# Power.net
KiCad netlist of a schematic drawn in Altium Designer
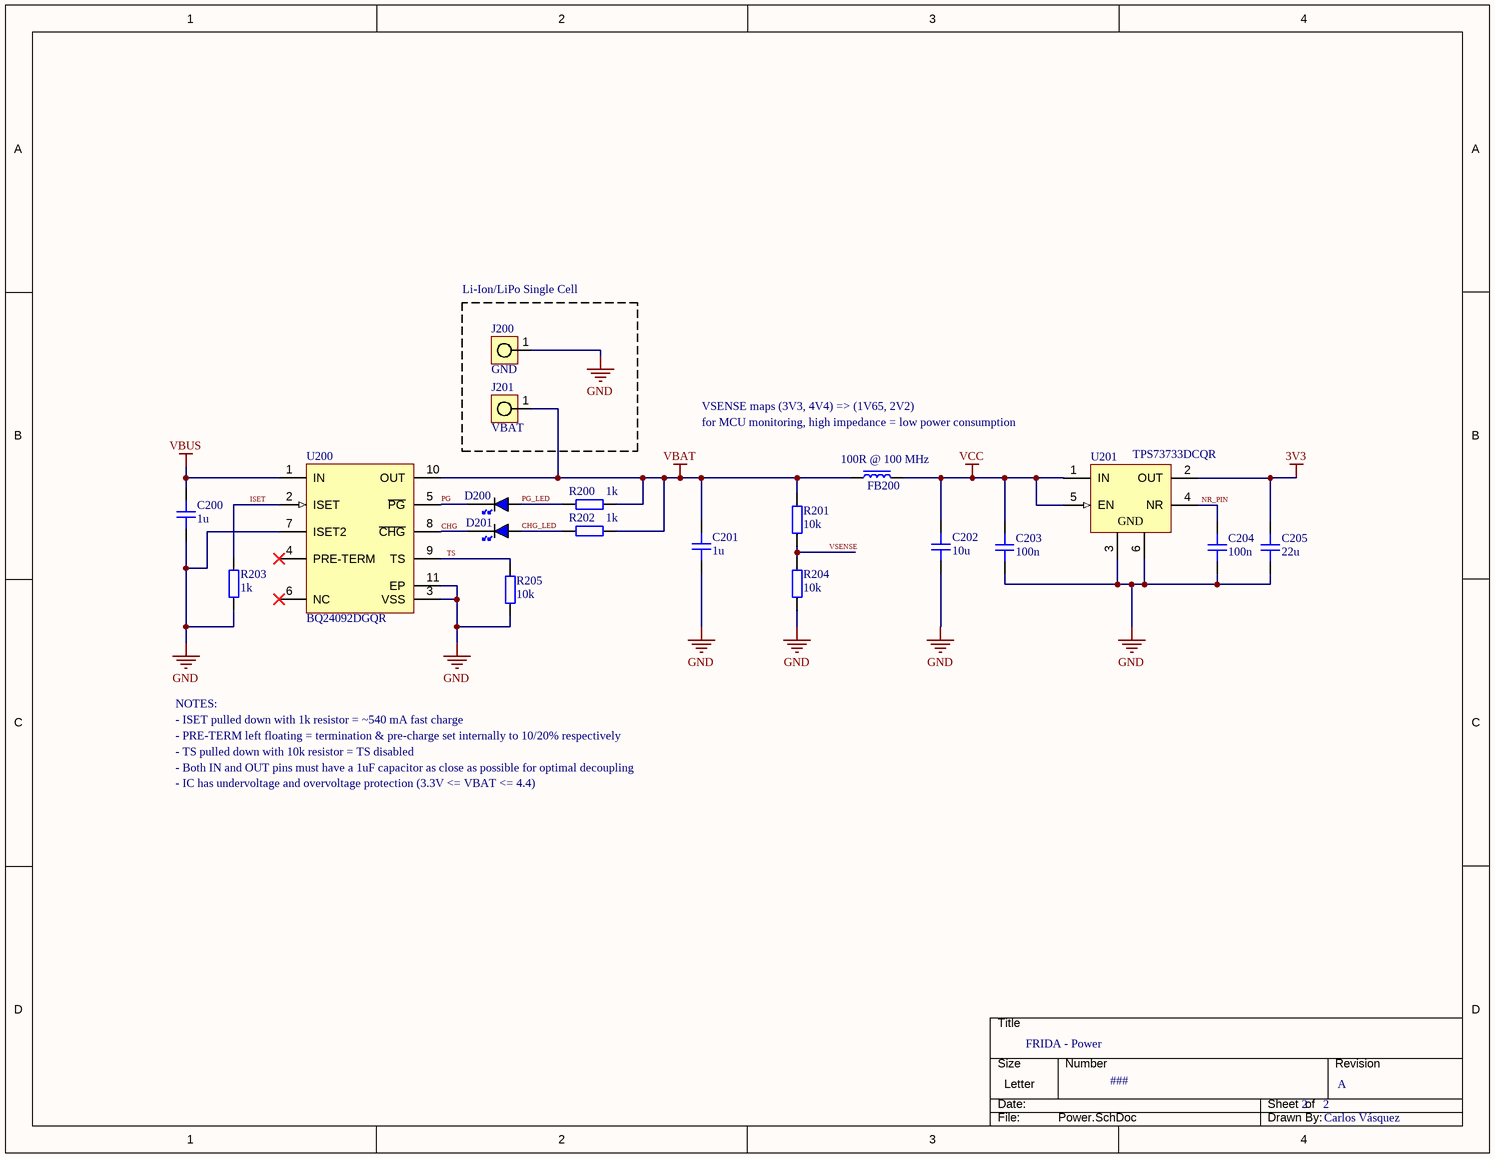
[diagram p0: Power.SchDoc]

(export (version "E")
  (design (tool "Eeschema 10.0.6"))
  (components
    (comp (ref "C200")
      (value "1u")
      (footprint "CAP_0402")
      (description "Capacitor SMD 0402")
      (libsource (lib "Schematic-Lib-PhilsLab") (part "CAP_0402"))
    )
    (comp (ref "C201")
      (value "1u")
      (footprint "CAP_0402")
      (description "Capacitor SMD 0402")
      (libsource (lib "Schematic-Lib-PhilsLab") (part "CAP_0402"))
    )
    (comp (ref "C202")
      (value "10u")
      (footprint "CAP_0805")
      (description "Capacitor SMD 0805")
      (libsource (lib "Schematic-Lib-PhilsLab") (part "CAP_0805"))
    )
    (comp (ref "C203")
      (value "100n")
      (footprint "CAP_0603")
      (description "Capacitor SMD 0603")
      (libsource (lib "Schematic-Lib-PhilsLab") (part "CAP_0603"))
    )
    (comp (ref "C204")
      (value "100n")
      (footprint "CAP_0603")
      (description "Capacitor SMD 0603")
      (libsource (lib "Schematic-Lib-PhilsLab") (part "CAP_0603"))
    )
    (comp (ref "C205")
      (value "22u")
      (footprint "CAP_0603")
      (description "Capacitor SMD 0603")
      (libsource (lib "Schematic-Lib-PhilsLab") (part "CAP_0603"))
    )
    (comp (ref "D200")
      (value "BLUE")
      (footprint "LED_0805_BLUE")
      (description "LED 0805 BLUE SMD")
      (libsource (lib "Schematic-Lib-PhilsLab") (part "LED_0805_BLUE"))
    )
    (comp (ref "D201")
      (value "BLUE")
      (footprint "LED_0805_BLUE")
      (description "LED 0805 BLUE SMD")
      (libsource (lib "Schematic-Lib-PhilsLab") (part "LED_0805_BLUE"))
    )
    (comp (ref "FB200")
      (value "100R @ 100 MHz")
      (footprint "FB_0805")
      (description "Ferrite Bead SMD 0805")
      (libsource (lib "Schematic-Lib-PhilsLab") (part "FB_0805"))
    )
    (comp (ref "J200")
      (value "GND")
      (footprint "SOLDER_PIN_THT_1_5")
      (description "Solder Pin 1.5mm Through-Hole")
      (libsource (lib "Schematic-Lib-PhilsLab") (part "SOLDER_PIN_THT"))
    )
    (comp (ref "J201")
      (value "VBAT")
      (footprint "SOLDER_PIN_THT_1_5")
      (description "Solder Pin 1.5mm Through-Hole")
      (libsource (lib "Schematic-Lib-PhilsLab") (part "SOLDER_PIN_THT"))
    )
    (comp (ref "R200")
      (value "1k")
      (footprint "RES_0402")
      (description "Resistor SMD 0402")
      (libsource (lib "Schematic-Lib-PhilsLab") (part "RES_0402"))
    )
    (comp (ref "R201")
      (value "10k")
      (footprint "RES_0402")
      (description "Resistor SMD 0402")
      (libsource (lib "Schematic-Lib-PhilsLab") (part "RES_0402"))
    )
    (comp (ref "R202")
      (value "1k")
      (footprint "RES_0402")
      (description "Resistor SMD 0402")
      (libsource (lib "Schematic-Lib-PhilsLab") (part "RES_0402"))
    )
    (comp (ref "R203")
      (value "1k")
      (footprint "RES_0402")
      (description "Resistor SMD 0402")
      (libsource (lib "Schematic-Lib-PhilsLab") (part "RES_0402"))
    )
    (comp (ref "R204")
      (value "10k")
      (footprint "RES_0402")
      (description "Resistor SMD 0402")
      (libsource (lib "Schematic-Lib-PhilsLab") (part "RES_0402"))
    )
    (comp (ref "R205")
      (value "10k")
      (footprint "RES_0402")
      (description "Resistor SMD 0402")
      (libsource (lib "Schematic-Lib-PhilsLab") (part "RES_0402"))
    )
    (comp (ref "U200")
      (value "BQ24092DGQR")
      (footprint "DGQ0010D_L")
      (fields (field (name "MANUFACTURER") "Texas Instruments"))
      (libsource (lib "Altium Content Vault") (part "TI-BQ24092DGQ10-1675X1445TP"))
    )
    (comp (ref "U201")
      (value "TPS73733DCQR")
      (footprint "DCQ0006A_N")
      (fields (field (name "MANUFACTURER") "Texas Instruments"))
      (libsource (lib "Altium Content Vault") (part "TI-TPS73XXXDCQ6"))
    )
  )
  (nets
    (net (code "1") (name "/CHG") (class "Default")
      (node (ref "D201") (pin "K") (pinfunction "K_K") (pintype "passive"))
      (node (ref "U200") (pin "8") (pinfunction "~{CHG}_8") (pintype "tri_state"))
    )
    (net (code "2") (name "/CHG_LED") (class "Default")
      (node (ref "D201") (pin "A") (pinfunction "A_A") (pintype "passive"))
      (node (ref "R202") (pin "2") (pinfunction "2_2") (pintype "passive"))
    )
    (net (code "3") (name "/ISET") (class "Default")
      (node (ref "R203") (pin "1") (pinfunction "1_1") (pintype "passive"))
      (node (ref "U200") (pin "2") (pinfunction "ISET_2") (pintype "input"))
    )
    (net (code "4") (name "/NR_PIN") (class "Default")
      (node (ref "C204") (pin "2") (pinfunction "2_2") (pintype "passive"))
      (node (ref "U201") (pin "4") (pinfunction "NR_4") (pintype "passive"))
    )
    (net (code "5") (name "/PG") (class "Default")
      (node (ref "D200") (pin "K") (pinfunction "K_K") (pintype "passive"))
      (node (ref "U200") (pin "5") (pinfunction "~{PG}_5") (pintype "tri_state"))
    )
    (net (code "6") (name "/PG_LED") (class "Default")
      (node (ref "D200") (pin "A") (pinfunction "A_A") (pintype "passive"))
      (node (ref "R200") (pin "2") (pinfunction "2_2") (pintype "passive"))
    )
    (net (code "7") (name "/TS") (class "Default")
      (node (ref "R205") (pin "2") (pinfunction "2_2") (pintype "passive"))
      (node (ref "U200") (pin "9") (pinfunction "TS_9") (pintype "passive"))
    )
    (net (code "8") (name "/VSENSE") (class "Default")
      (node (ref "R201") (pin "1") (pinfunction "1_1") (pintype "passive"))
      (node (ref "R204") (pin "2") (pinfunction "2_2") (pintype "passive"))
    )
    (net (code "9") (name "3V3") (class "Default")
      (node (ref "C205") (pin "2") (pinfunction "2_2") (pintype "passive"))
      (node (ref "U201") (pin "2") (pinfunction "OUT_2") (pintype "power_in"))
    )
    (net (code "10") (name "GND") (class "Default")
      (node (ref "C200") (pin "1") (pinfunction "1_1") (pintype "passive"))
      (node (ref "C201") (pin "1") (pinfunction "1_1") (pintype "passive"))
      (node (ref "C202") (pin "1") (pinfunction "1_1") (pintype "passive"))
      (node (ref "C203") (pin "1") (pinfunction "1_1") (pintype "passive"))
      (node (ref "C204") (pin "1") (pinfunction "1_1") (pintype "passive"))
      (node (ref "C205") (pin "1") (pinfunction "1_1") (pintype "passive"))
      (node (ref "J200") (pin "1") (pinfunction "1_1") (pintype "passive"))
      (node (ref "R203") (pin "2") (pinfunction "2_2") (pintype "passive"))
      (node (ref "R204") (pin "1") (pinfunction "1_1") (pintype "passive"))
      (node (ref "R205") (pin "1") (pinfunction "1_1") (pintype "passive"))
      (node (ref "U200") (pin "11") (pinfunction "EP_11") (pintype "power_in"))
      (node (ref "U200") (pin "3") (pinfunction "VSS_3") (pintype "power_in"))
      (node (ref "U200") (pin "7") (pinfunction "ISET2_7") (pintype "passive"))
      (node (ref "U201") (pin "3") (pinfunction "GND_3") (pintype "power_in"))
      (node (ref "U201") (pin "6") (pinfunction "GND_6") (pintype "power_in"))
    )
    (net (code "11") (name "VBAT") (class "Default")
      (node (ref "C201") (pin "2") (pinfunction "2_2") (pintype "passive"))
      (node (ref "FB200") (pin "1") (pinfunction "1_1") (pintype "passive"))
      (node (ref "J201") (pin "1") (pinfunction "1_1") (pintype "passive"))
      (node (ref "R200") (pin "1") (pinfunction "1_1") (pintype "passive"))
      (node (ref "R201") (pin "2") (pinfunction "2_2") (pintype "passive"))
      (node (ref "R202") (pin "1") (pinfunction "1_1") (pintype "passive"))
      (node (ref "U200") (pin "10") (pinfunction "OUT_10") (pintype "power_in"))
    )
    (net (code "12") (name "VBUS") (class "Default")
      (node (ref "C200") (pin "2") (pinfunction "2_2") (pintype "passive"))
      (node (ref "U200") (pin "1") (pinfunction "IN_1") (pintype "power_in"))
    )
    (net (code "13") (name "VCC") (class "Default")
      (node (ref "C202") (pin "2") (pinfunction "2_2") (pintype "passive"))
      (node (ref "C203") (pin "2") (pinfunction "2_2") (pintype "passive"))
      (node (ref "FB200") (pin "2") (pinfunction "2_2") (pintype "passive"))
      (node (ref "U201") (pin "1") (pinfunction "IN_1") (pintype "power_in"))
      (node (ref "U201") (pin "5") (pinfunction "EN_5") (pintype "input"))
    )
    (net (code "14") (name "unconnected-(U200-NC-Pad6)") (class "Default")
      (node (ref "U200") (pin "6") (pinfunction "NC_6") (pintype "passive+no_connect"))
    )
    (net (code "15") (name "unconnected-(U200-PRE-TERM-Pad4)") (class "Default")
      (node (ref "U200") (pin "4") (pinfunction "PRE-TERM_4") (pintype "passive+no_connect"))
    )
  )
)
